# Sheet2_COM.net
KiCad netlist of a schematic drawn in Altium Designer
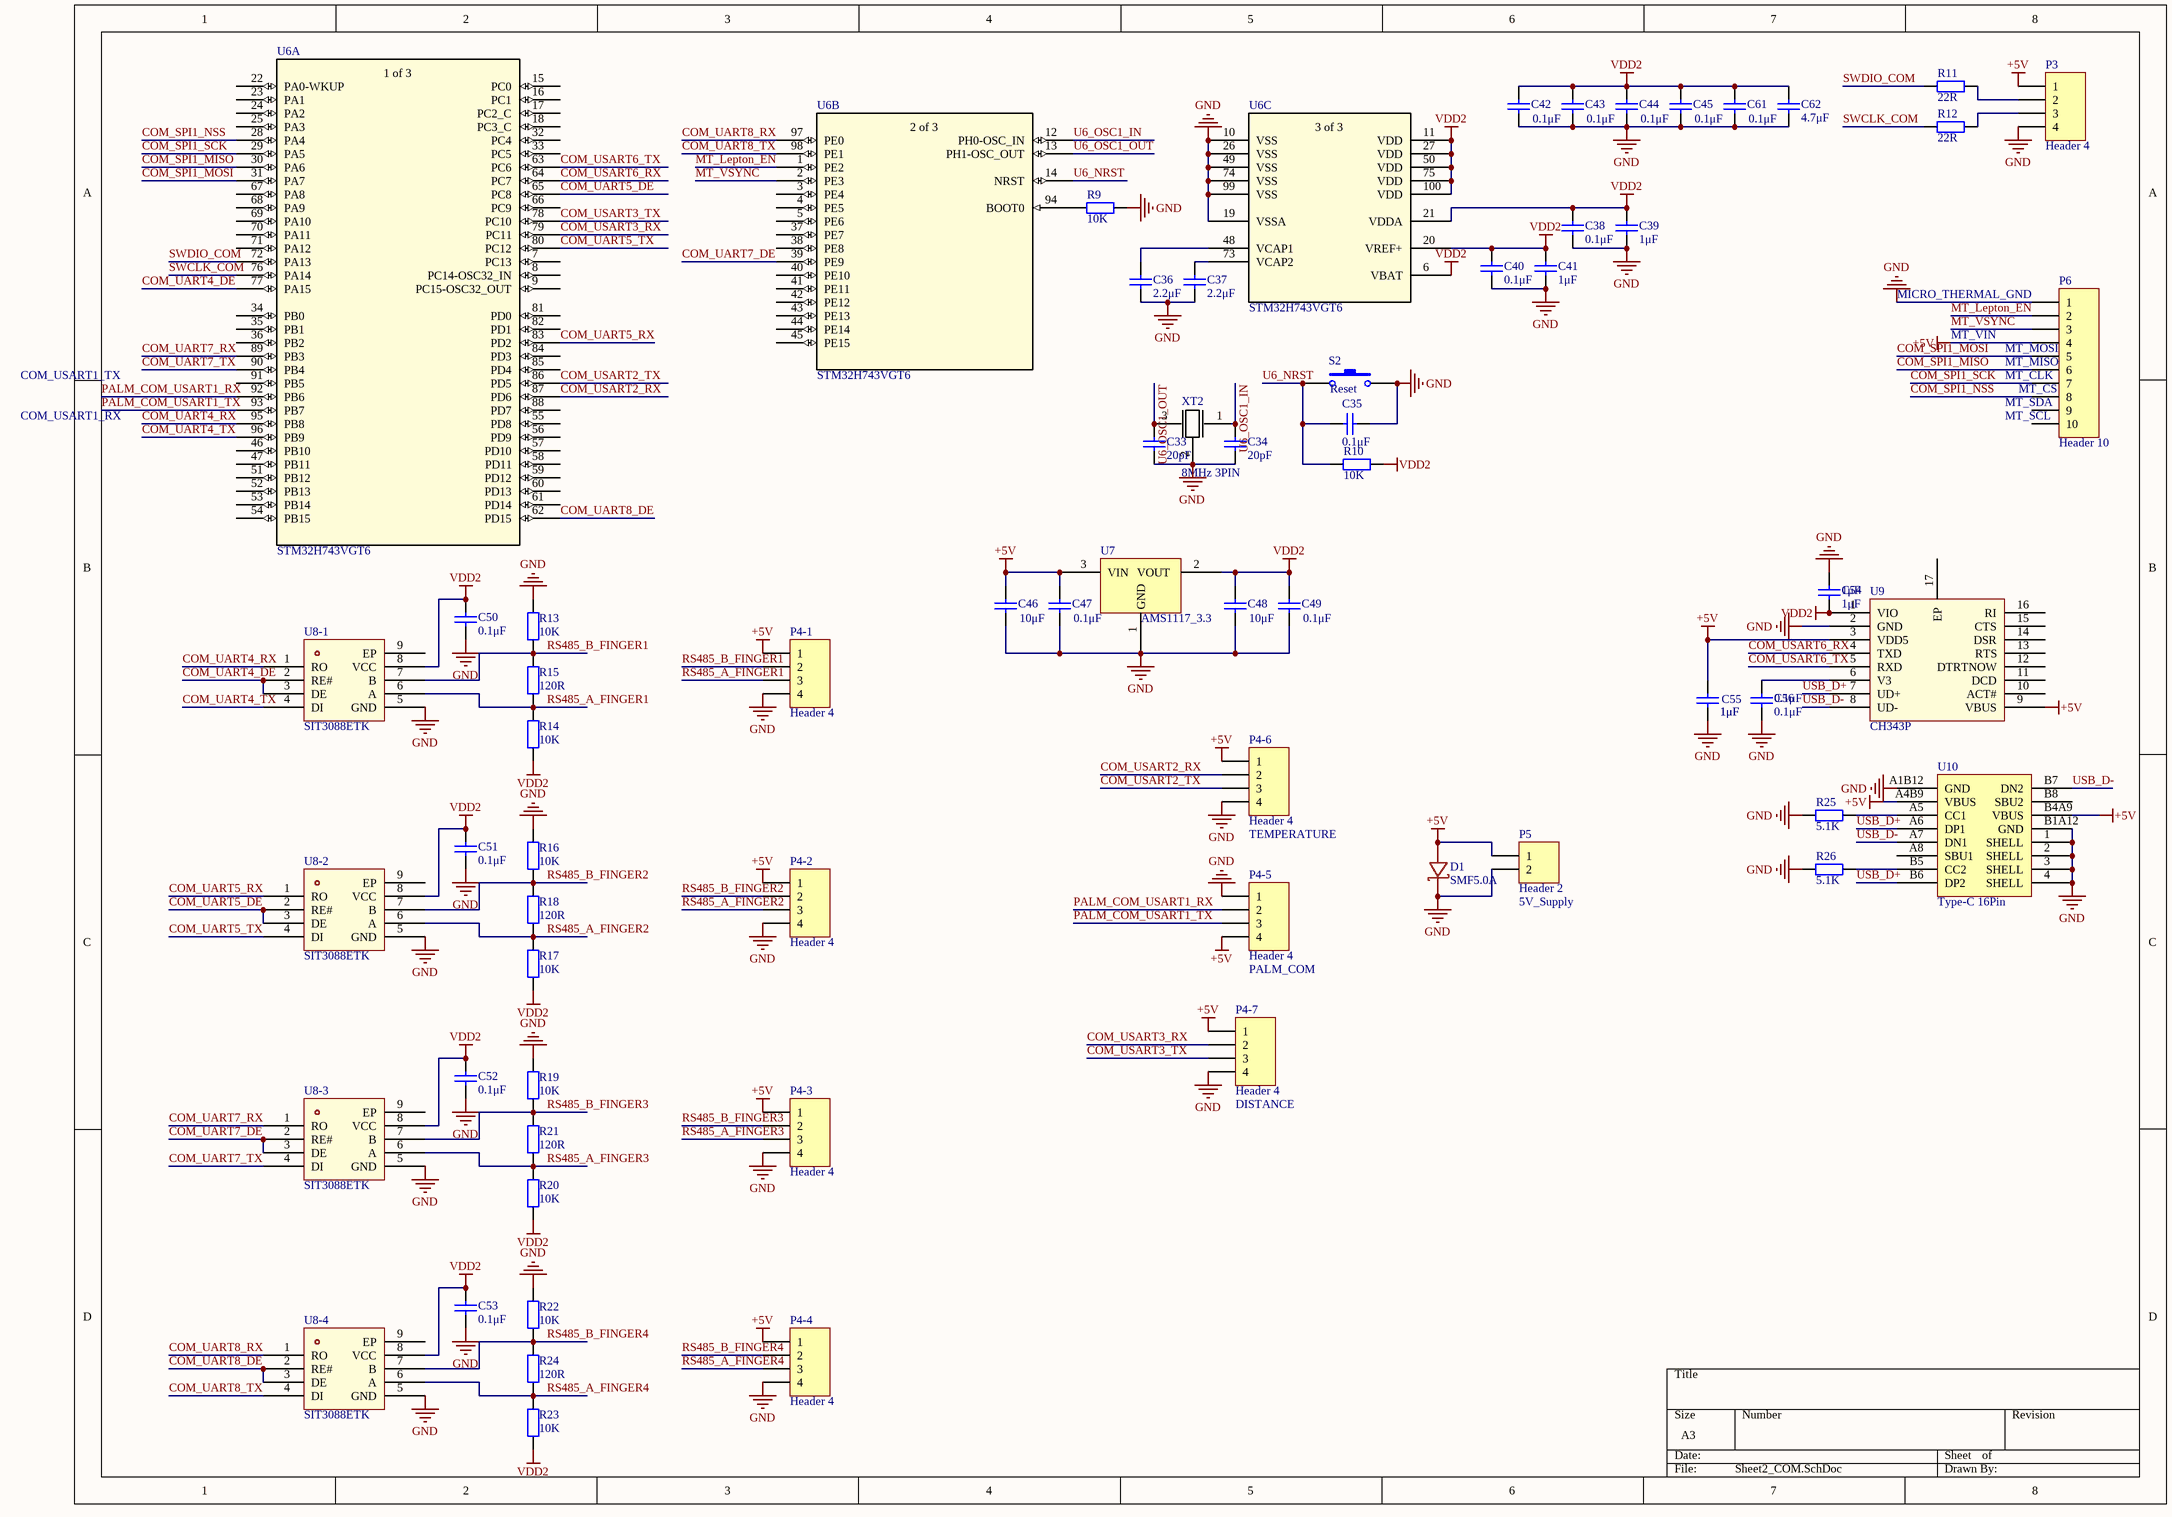
[diagram p0: Sheet2_COM.SchDoc]

(export (version "E")
  (design (tool "Eeschema 10.0.6"))
  (components
    (comp (ref "C33")
      (value "20pF")
      (footprint "C0402")
      (description "Capacitor (Semiconductor SIM Model)")
      (fields (field (name "PUBLISHER") "Altium Limited"))
      (libsource (lib "Miscellaneous Devices") (part "Cap Semi"))
    )
    (comp (ref "C34")
      (value "20pF")
      (footprint "C0402")
      (description "Capacitor (Semiconductor SIM Model)")
      (fields (field (name "PUBLISHER") "Altium Limited"))
      (libsource (lib "Miscellaneous Devices") (part "Cap Semi"))
    )
    (comp (ref "C35")
      (value "0.1μF")
      (footprint "C0402")
      (description "Capacitor (Semiconductor SIM Model)")
      (fields (field (name "PUBLISHER") "Altium Limited"))
      (libsource (lib "Miscellaneous Devices") (part "Cap Semi"))
    )
    (comp (ref "C36")
      (value "2.2μF")
      (footprint "C0402")
      (description "Capacitor (Semiconductor SIM Model)")
      (fields (field (name "PUBLISHER") "Altium Limited"))
      (libsource (lib "Miscellaneous Devices") (part "Cap Semi"))
    )
    (comp (ref "C37")
      (value "2.2μF")
      (footprint "C0402")
      (description "Capacitor (Semiconductor SIM Model)")
      (fields (field (name "PUBLISHER") "Altium Limited"))
      (libsource (lib "Miscellaneous Devices") (part "Cap Semi"))
    )
    (comp (ref "C38")
      (value "0.1μF")
      (footprint "C0402")
      (description "Capacitor (Semiconductor SIM Model)")
      (fields (field (name "PUBLISHER") "Altium Limited"))
      (libsource (lib "Miscellaneous Devices") (part "Cap Semi"))
    )
    (comp (ref "C39")
      (value "1μF")
      (footprint "C0402")
      (description "Capacitor (Semiconductor SIM Model)")
      (fields (field (name "PUBLISHER") "Altium Limited"))
      (libsource (lib "Miscellaneous Devices") (part "Cap Semi"))
    )
    (comp (ref "C40")
      (value "0.1μF")
      (footprint "C0402")
      (description "Capacitor (Semiconductor SIM Model)")
      (fields (field (name "PUBLISHER") "Altium Limited"))
      (libsource (lib "Miscellaneous Devices") (part "Cap Semi"))
    )
    (comp (ref "C41")
      (value "1μF")
      (footprint "C0402")
      (description "Capacitor (Semiconductor SIM Model)")
      (fields (field (name "PUBLISHER") "Altium Limited"))
      (libsource (lib "Miscellaneous Devices") (part "Cap Semi"))
    )
    (comp (ref "C42")
      (value "0.1μF")
      (footprint "C0402")
      (description "Capacitor (Semiconductor SIM Model)")
      (fields (field (name "PUBLISHER") "Altium Limited"))
      (libsource (lib "Miscellaneous Devices") (part "Cap Semi"))
    )
    (comp (ref "C43")
      (value "0.1μF")
      (footprint "C0402")
      (description "Capacitor (Semiconductor SIM Model)")
      (fields (field (name "PUBLISHER") "Altium Limited"))
      (libsource (lib "Miscellaneous Devices") (part "Cap Semi"))
    )
    (comp (ref "C44")
      (value "0.1μF")
      (footprint "C0402")
      (description "Capacitor (Semiconductor SIM Model)")
      (fields (field (name "PUBLISHER") "Altium Limited"))
      (libsource (lib "Miscellaneous Devices") (part "Cap Semi"))
    )
    (comp (ref "C45")
      (value "0.1μF")
      (footprint "C0402")
      (description "Capacitor (Semiconductor SIM Model)")
      (fields (field (name "PUBLISHER") "Altium Limited"))
      (libsource (lib "Miscellaneous Devices") (part "Cap Semi"))
    )
    (comp (ref "C46")
      (value "10μF")
      (footprint "C0402")
      (description "Capacitor (Semiconductor SIM Model)")
      (fields (field (name "PUBLISHER") "Altium Limited"))
      (libsource (lib "Miscellaneous Devices") (part "Cap Semi"))
    )
    (comp (ref "C47")
      (value "0.1μF")
      (footprint "C0402")
      (description "Capacitor (Semiconductor SIM Model)")
      (fields (field (name "PUBLISHER") "Altium Limited"))
      (libsource (lib "Miscellaneous Devices") (part "Cap Semi"))
    )
    (comp (ref "C48")
      (value "10μF")
      (footprint "C0402")
      (description "Capacitor (Semiconductor SIM Model)")
      (fields (field (name "PUBLISHER") "Altium Limited"))
      (libsource (lib "Miscellaneous Devices") (part "Cap Semi"))
    )
    (comp (ref "C49")
      (value "0.1μF")
      (footprint "C0402")
      (description "Capacitor (Semiconductor SIM Model)")
      (fields (field (name "PUBLISHER") "Altium Limited"))
      (libsource (lib "Miscellaneous Devices") (part "Cap Semi"))
    )
    (comp (ref "C50")
      (value "0.1μF")
      (footprint "C0402")
      (description "Capacitor (Semiconductor SIM Model)")
      (fields (field (name "PUBLISHER") "Altium Limited"))
      (libsource (lib "Miscellaneous Devices") (part "Cap Semi"))
    )
    (comp (ref "C51")
      (value "0.1μF")
      (footprint "C0402")
      (description "Capacitor (Semiconductor SIM Model)")
      (fields (field (name "PUBLISHER") "Altium Limited"))
      (libsource (lib "Miscellaneous Devices") (part "Cap Semi"))
    )
    (comp (ref "C52")
      (value "0.1μF")
      (footprint "C0402")
      (description "Capacitor (Semiconductor SIM Model)")
      (fields (field (name "PUBLISHER") "Altium Limited"))
      (libsource (lib "Miscellaneous Devices") (part "Cap Semi"))
    )
    (comp (ref "C53")
      (value "0.1μF")
      (footprint "C0402")
      (description "Capacitor (Semiconductor SIM Model)")
      (fields (field (name "PUBLISHER") "Altium Limited"))
      (libsource (lib "Miscellaneous Devices") (part "Cap Semi"))
    )
    (comp (ref "C54")
      (value "1μF")
      (footprint "C0402")
      (description "Capacitor (Semiconductor SIM Model)")
      (fields (field (name "ALTIUM_VALUE") "1μF") (field (name "PUBLISHER") "Altium Limited"))
      (libsource (lib "Miscellaneous Devices") (part "Cap Semi"))
    )
    (comp (ref "C55")
      (value "1μF")
      (footprint "C0402")
      (description "Capacitor (Semiconductor SIM Model)")
      (fields (field (name "ALTIUM_VALUE") "1μF") (field (name "PUBLISHER") "Altium Limited"))
      (libsource (lib "Miscellaneous Devices") (part "Cap Semi"))
    )
    (comp (ref "C56")
      (value "0.1μF")
      (footprint "C0402")
      (description "Capacitor (Semiconductor SIM Model)")
      (fields (field (name "ALTIUM_VALUE") "0.1μF") (field (name "PUBLISHER") "Altium Limited"))
      (libsource (lib "Miscellaneous Devices") (part "Cap Semi"))
    )
    (comp (ref "C61")
      (value "0.1μF")
      (footprint "C0402")
      (description "Capacitor (Semiconductor SIM Model)")
      (fields (field (name "PUBLISHER") "Altium Limited"))
      (libsource (lib "Miscellaneous Devices") (part "Cap Semi"))
    )
    (comp (ref "C62")
      (value "4.7μF")
      (footprint "C0402")
      (description "Capacitor (Semiconductor SIM Model)")
      (fields (field (name "PUBLISHER") "Altium Limited"))
      (libsource (lib "Miscellaneous Devices") (part "Cap Semi"))
    )
    (comp (ref "D1")
      (value "SMF5.0A")
      (footprint "SOD-123FL_L2.7-W1.8-LS3.8-RD")
      (libsource (lib "Basic") (part "SMF5.0A"))
    )
    (comp (ref "P3")
      (value "Header 4")
      (footprint "CONN-SMD_XDWF-0910-04P")
      (description "XDWF-0910-04P")
      (fields (field (name "PUBLISHER") "Altium Limited"))
      (libsource (lib "Miscellaneous Connectors") (part "Header 4"))
    )
    (comp (ref "P4-1")
      (value "Header 4")
      (footprint "CONN-SMD_XDWF-0910-04P")
      (description "XDWF-0910-04P")
      (fields (field (name "PUBLISHER") "Altium Limited"))
      (libsource (lib "Miscellaneous Connectors") (part "Header 4"))
    )
    (comp (ref "P4-2")
      (value "Header 4")
      (footprint "CONN-SMD_XDWF-0910-04P")
      (description "XDWF-0910-04P")
      (fields (field (name "PUBLISHER") "Altium Limited"))
      (libsource (lib "Miscellaneous Connectors") (part "Header 4"))
    )
    (comp (ref "P4-3")
      (value "Header 4")
      (footprint "CONN-SMD_XDWF-0910-04P")
      (description "XDWF-0910-04P")
      (fields (field (name "PUBLISHER") "Altium Limited"))
      (libsource (lib "Miscellaneous Connectors") (part "Header 4"))
    )
    (comp (ref "P4-4")
      (value "Header 4")
      (footprint "CONN-SMD_XDWF-0910-04P")
      (description "XDWF-0910-04P")
      (fields (field (name "PUBLISHER") "Altium Limited"))
      (libsource (lib "Miscellaneous Connectors") (part "Header 4"))
    )
    (comp (ref "P4-5")
      (value "Header 4")
      (footprint "HDR1X4")
      (description "Header, 4-Pin")
      (fields (field (name "PUBLISHER") "Altium Limited"))
      (libsource (lib "Miscellaneous Connectors") (part "Header 4"))
    )
    (comp (ref "P4-6")
      (value "Header 4")
      (footprint "CONN-SMD_XDWF-0910-04P")
      (description "XDWF-0910-04P")
      (fields (field (name "PUBLISHER") "Altium Limited"))
      (libsource (lib "Miscellaneous Connectors") (part "Header 4"))
    )
    (comp (ref "P4-7")
      (value "Header 4")
      (footprint "CONN-SMD_XDWF-0910-04P")
      (description "XDWF-0910-04P")
      (fields (field (name "PUBLISHER") "Altium Limited"))
      (libsource (lib "Miscellaneous Connectors") (part "Header 4"))
    )
    (comp (ref "P5")
      (value "Header 2")
      (footprint "CONN-SMD_2060-452")
      (description "Header, 2-Pin")
      (fields (field (name "PUBLISHER") "Altium Limited"))
      (libsource (lib "Miscellaneous Connectors") (part "Header 2"))
    )
    (comp (ref "P6")
      (value "Header 10")
      (footprint "FPC-SMD_10P-P0.50_HCTL_HC-FPC-05-10-10RLTAG")
      (description "Header, 10-Pin")
      (fields (field (name "PUBLISHER") "Altium Limited"))
      (libsource (lib "Miscellaneous Connectors") (part "Header 10"))
    )
    (comp (ref "R9")
      (value "10K")
      (footprint "R0402")
      (description "Resistor")
      (fields (field (name "PUBLISHER") "Altium Limited"))
      (libsource (lib "") (part "Res2_3"))
    )
    (comp (ref "R10")
      (value "10K")
      (footprint "R0402")
      (description "Resistor")
      (fields (field (name "PUBLISHER") "Altium Limited"))
      (libsource (lib "Miscellaneous Devices") (part "Res2"))
    )
    (comp (ref "R11")
      (value "22R")
      (footprint "R0402")
      (description "Resistor")
      (fields (field (name "PUBLISHER") "Altium Limited"))
      (libsource (lib "Miscellaneous Devices") (part "Res2"))
    )
    (comp (ref "R12")
      (value "22R")
      (footprint "R0402")
      (description "Resistor")
      (fields (field (name "PUBLISHER") "Altium Limited"))
      (libsource (lib "Miscellaneous Devices") (part "Res2"))
    )
    (comp (ref "R13")
      (value "10K")
      (footprint "R0402")
      (description "Resistor")
      (fields (field (name "PUBLISHER") "Altium Limited"))
      (libsource (lib "") (part "Res2_1"))
    )
    (comp (ref "R14")
      (value "10K")
      (footprint "R0402")
      (description "Resistor")
      (fields (field (name "PUBLISHER") "Altium Limited"))
      (libsource (lib "") (part "Res2_1"))
    )
    (comp (ref "R15")
      (value "120R")
      (footprint "R0402")
      (description "Resistor")
      (fields (field (name "PUBLISHER") "Altium Limited"))
      (libsource (lib "") (part "Res2_2"))
    )
    (comp (ref "R16")
      (value "10K")
      (footprint "R0402")
      (description "Resistor")
      (fields (field (name "PUBLISHER") "Altium Limited"))
      (libsource (lib "") (part "Res2_1"))
    )
    (comp (ref "R17")
      (value "10K")
      (footprint "R0402")
      (description "Resistor")
      (fields (field (name "PUBLISHER") "Altium Limited"))
      (libsource (lib "") (part "Res2_1"))
    )
    (comp (ref "R18")
      (value "120R")
      (footprint "R0402")
      (description "Resistor")
      (fields (field (name "PUBLISHER") "Altium Limited"))
      (libsource (lib "") (part "Res2_2"))
    )
    (comp (ref "R19")
      (value "10K")
      (footprint "R0402")
      (description "Resistor")
      (fields (field (name "PUBLISHER") "Altium Limited"))
      (libsource (lib "") (part "Res2_1"))
    )
    (comp (ref "R20")
      (value "10K")
      (footprint "R0402")
      (description "Resistor")
      (fields (field (name "PUBLISHER") "Altium Limited"))
      (libsource (lib "") (part "Res2_1"))
    )
    (comp (ref "R21")
      (value "120R")
      (footprint "R0402")
      (description "Resistor")
      (fields (field (name "PUBLISHER") "Altium Limited"))
      (libsource (lib "") (part "Res2_2"))
    )
    (comp (ref "R22")
      (value "10K")
      (footprint "R0402")
      (description "Resistor")
      (fields (field (name "PUBLISHER") "Altium Limited"))
      (libsource (lib "") (part "Res2_1"))
    )
    (comp (ref "R23")
      (value "10K")
      (footprint "R0402")
      (description "Resistor")
      (fields (field (name "PUBLISHER") "Altium Limited"))
      (libsource (lib "") (part "Res2_1"))
    )
    (comp (ref "R24")
      (value "120R")
      (footprint "R0402")
      (description "Resistor")
      (fields (field (name "PUBLISHER") "Altium Limited"))
      (libsource (lib "") (part "Res2_2"))
    )
    (comp (ref "R25")
      (value "5.1K")
      (footprint "R0402")
      (description "Resistor")
      (fields (field (name "PUBLISHER") "Altium Limited"))
      (libsource (lib "Miscellaneous Devices") (part "Res2"))
    )
    (comp (ref "R26")
      (value "5.1K")
      (footprint "R0402")
      (description "Resistor")
      (fields (field (name "PUBLISHER") "Altium Limited"))
      (libsource (lib "Miscellaneous Devices") (part "Res2"))
    )
    (comp (ref "S2")
      (value "Reset")
      (footprint "SW-SMD_L3.9-W3.0-P4.45")
      (description "TS-1088R-02026")
      (fields (field (name "PUBLISHER") "Altium Limited"))
      (libsource (lib "Miscellaneous Devices") (part "SW-PB"))
    )
    (comp (ref "U6")
      (value "STM32H743VGT6")
      (footprint "LQFP100-14x14mm")
      (description "No Description Available")
      (libsource (lib "STM32H743VGT6") (part "STM32H743VGT6"))
    )
    (comp (ref "U7")
      (value "AMS1117_3.3")
      (footprint "AMS1117-3.3")
      (libsource (lib "Schlib1") (part "AMS1117_3.3 SOT-89"))
    )
    (comp (ref "U8-1")
      (value "SIT3088ETK")
      (footprint "DFN-8_L3.0-W3.0-P0.65-BL-EP")
      (libsource (lib "Basic") (part "SIT3088ETK"))
    )
    (comp (ref "U8-2")
      (value "SIT3088ETK")
      (footprint "DFN-8_L3.0-W3.0-P0.65-BL-EP")
      (libsource (lib "Basic") (part "SIT3088ETK"))
    )
    (comp (ref "U8-3")
      (value "SIT3088ETK")
      (footprint "DFN-8_L3.0-W3.0-P0.65-BL-EP")
      (libsource (lib "Basic") (part "SIT3088ETK"))
    )
    (comp (ref "U8-4")
      (value "SIT3088ETK")
      (footprint "DFN-8_L3.0-W3.0-P0.65-BL-EP")
      (libsource (lib "Basic") (part "SIT3088ETK"))
    )
    (comp (ref "U9") (value "CH343P") (footprint "CH343P") (libsource (lib "Schlibs") (part "CH343P")))
    (comp (ref "U10")
      (value "Type-C 16Pin")
      (footprint "USB-C-SMD_TYPE-C16PIN")
      (libsource (lib "Schlib1") (part "Type-C 16Pin"))
    )
    (comp (ref "XT2")
      (value "8MHz 3PIN")
      (footprint "8MHz 0.07% OSC-SMD_3P-L3.2-W1.3-P1.20-L")
      (description "CSTNE8M00GH5C000R0")
      (libsource (lib "Schlibs") (part "8MHz 0.07% 3PIN_1"))
    )
  )
  (nets
    (net (code "1") (name "+5V") (class "Default")
      (node (ref "C46") (pin "2") (pinfunction "2_2") (pintype "passive"))
      (node (ref "C47") (pin "2") (pinfunction "2_2") (pintype "passive"))
      (node (ref "C55") (pin "2") (pinfunction "2_2") (pintype "passive"))
      (node (ref "D1") (pin "2") (pinfunction "A_2") (pintype "passive"))
      (node (ref "P3") (pin "1") (pinfunction "1_1") (pintype "passive"))
      (node (ref "P4-1") (pin "1") (pinfunction "1_1") (pintype "passive"))
      (node (ref "P4-2") (pin "1") (pinfunction "1_1") (pintype "passive"))
      (node (ref "P4-3") (pin "1") (pinfunction "1_1") (pintype "passive"))
      (node (ref "P4-4") (pin "1") (pinfunction "1_1") (pintype "passive"))
      (node (ref "P4-5") (pin "4") (pinfunction "4_4") (pintype "passive"))
      (node (ref "P4-6") (pin "1") (pinfunction "1_1") (pintype "passive"))
      (node (ref "P4-7") (pin "1") (pinfunction "1_1") (pintype "passive"))
      (node (ref "P5") (pin "1") (pinfunction "1_1") (pintype "passive"))
      (node (ref "P6") (pin "4") (pinfunction "4_4") (pintype "passive"))
      (node (ref "U10") (pin "A4B9") (pinfunction "VBUS_A4B9") (pintype "passive"))
      (node (ref "U10") (pin "B4A9") (pinfunction "VBUS_B4A9") (pintype "passive"))
      (node (ref "U7") (pin "3") (pinfunction "VIN_3") (pintype "passive"))
      (node (ref "U9") (pin "3") (pinfunction "VDD5_3") (pintype "passive"))
      (node (ref "U9") (pin "9") (pinfunction "VBUS_9") (pintype "passive"))
    )
    (net (code "2") (name "/COM_SPI1_MISO") (class "Default")
      (node (ref "P6") (pin "6") (pinfunction "6_6") (pintype "passive"))
      (node (ref "U6") (pin "30") (pinfunction "PA6_30") (pintype "bidirectional"))
    )
    (net (code "3") (name "/COM_SPI1_MOSI") (class "Default")
      (node (ref "P6") (pin "5") (pinfunction "5_5") (pintype "passive"))
      (node (ref "U6") (pin "31") (pinfunction "PA7_31") (pintype "bidirectional"))
    )
    (net (code "4") (name "/COM_SPI1_NSS") (class "Default")
      (node (ref "P6") (pin "8") (pinfunction "8_8") (pintype "passive"))
      (node (ref "U6") (pin "28") (pinfunction "PA4_28") (pintype "bidirectional"))
    )
    (net (code "5") (name "/COM_SPI1_SCK") (class "Default")
      (node (ref "P6") (pin "7") (pinfunction "7_7") (pintype "passive"))
      (node (ref "U6") (pin "29") (pinfunction "PA5_29") (pintype "bidirectional"))
    )
    (net (code "6") (name "/COM_UART4_DE") (class "Default")
      (node (ref "U6") (pin "77") (pinfunction "PA15_77") (pintype "bidirectional"))
      (node (ref "U8-1") (pin "2") (pinfunction "RE#_2") (pintype "passive"))
      (node (ref "U8-1") (pin "3") (pinfunction "DE_3") (pintype "passive"))
    )
    (net (code "7") (name "/COM_UART4_RX") (class "Default")
      (node (ref "U6") (pin "95") (pinfunction "PB8_95") (pintype "bidirectional"))
      (node (ref "U8-1") (pin "1") (pinfunction "RO_1") (pintype "passive"))
    )
    (net (code "8") (name "/COM_UART4_TX") (class "Default")
      (node (ref "U6") (pin "96") (pinfunction "PB9_96") (pintype "bidirectional"))
      (node (ref "U8-1") (pin "4") (pinfunction "DI_4") (pintype "passive"))
    )
    (net (code "9") (name "/COM_UART5_DE") (class "Default")
      (node (ref "U6") (pin "65") (pinfunction "PC8_65") (pintype "bidirectional"))
      (node (ref "U8-2") (pin "2") (pinfunction "RE#_2") (pintype "passive"))
      (node (ref "U8-2") (pin "3") (pinfunction "DE_3") (pintype "passive"))
    )
    (net (code "10") (name "/COM_UART5_RX") (class "Default")
      (node (ref "U6") (pin "83") (pinfunction "PD2_83") (pintype "bidirectional"))
      (node (ref "U8-2") (pin "1") (pinfunction "RO_1") (pintype "passive"))
    )
    (net (code "11") (name "/COM_UART5_TX") (class "Default")
      (node (ref "U6") (pin "80") (pinfunction "PC12_80") (pintype "bidirectional"))
      (node (ref "U8-2") (pin "4") (pinfunction "DI_4") (pintype "passive"))
    )
    (net (code "12") (name "/COM_UART7_DE") (class "Default")
      (node (ref "U6") (pin "39") (pinfunction "PE9_39") (pintype "bidirectional"))
      (node (ref "U8-3") (pin "2") (pinfunction "RE#_2") (pintype "passive"))
      (node (ref "U8-3") (pin "3") (pinfunction "DE_3") (pintype "passive"))
    )
    (net (code "13") (name "/COM_UART7_RX") (class "Default")
      (node (ref "U6") (pin "89") (pinfunction "PB3_89") (pintype "bidirectional"))
      (node (ref "U8-3") (pin "1") (pinfunction "RO_1") (pintype "passive"))
    )
    (net (code "14") (name "/COM_UART7_TX") (class "Default")
      (node (ref "U6") (pin "90") (pinfunction "PB4_90") (pintype "bidirectional"))
      (node (ref "U8-3") (pin "4") (pinfunction "DI_4") (pintype "passive"))
    )
    (net (code "15") (name "/COM_UART8_DE") (class "Default")
      (node (ref "U6") (pin "62") (pinfunction "PD15_62") (pintype "bidirectional"))
      (node (ref "U8-4") (pin "2") (pinfunction "RE#_2") (pintype "passive"))
      (node (ref "U8-4") (pin "3") (pinfunction "DE_3") (pintype "passive"))
    )
    (net (code "16") (name "/COM_UART8_RX") (class "Default")
      (node (ref "U6") (pin "97") (pinfunction "PE0_97") (pintype "bidirectional"))
      (node (ref "U8-4") (pin "1") (pinfunction "RO_1") (pintype "passive"))
    )
    (net (code "17") (name "/COM_UART8_TX") (class "Default")
      (node (ref "U6") (pin "98") (pinfunction "PE1_98") (pintype "bidirectional"))
      (node (ref "U8-4") (pin "4") (pinfunction "DI_4") (pintype "passive"))
    )
    (net (code "18") (name "/COM_USART2_RX") (class "Default")
      (node (ref "P4-6") (pin "2") (pinfunction "2_2") (pintype "passive"))
      (node (ref "U6") (pin "87") (pinfunction "PD6_87") (pintype "bidirectional"))
    )
    (net (code "19") (name "/COM_USART2_TX") (class "Default")
      (node (ref "P4-6") (pin "3") (pinfunction "3_3") (pintype "passive"))
      (node (ref "U6") (pin "86") (pinfunction "PD5_86") (pintype "bidirectional"))
    )
    (net (code "20") (name "/COM_USART3_RX") (class "Default")
      (node (ref "P4-7") (pin "2") (pinfunction "2_2") (pintype "passive"))
      (node (ref "U6") (pin "79") (pinfunction "PC11_79") (pintype "bidirectional"))
    )
    (net (code "21") (name "/COM_USART3_TX") (class "Default")
      (node (ref "P4-7") (pin "3") (pinfunction "3_3") (pintype "passive"))
      (node (ref "U6") (pin "78") (pinfunction "PC10_78") (pintype "bidirectional"))
    )
    (net (code "22") (name "/COM_USART6_RX") (class "Default")
      (node (ref "U6") (pin "64") (pinfunction "PC7_64") (pintype "bidirectional"))
      (node (ref "U9") (pin "4") (pinfunction "TXD_4") (pintype "passive"))
    )
    (net (code "23") (name "/COM_USART6_TX") (class "Default")
      (node (ref "U6") (pin "63") (pinfunction "PC6_63") (pintype "bidirectional"))
      (node (ref "U9") (pin "5") (pinfunction "RXD_5") (pintype "passive"))
    )
    (net (code "24") (name "/MT_Lepton_EN") (class "Default")
      (node (ref "P6") (pin "2") (pinfunction "2_2") (pintype "passive"))
      (node (ref "U6") (pin "1") (pinfunction "PE2_1") (pintype "bidirectional"))
    )
    (net (code "25") (name "/MT_VSYNC") (class "Default")
      (node (ref "P6") (pin "3") (pinfunction "3_3") (pintype "passive"))
      (node (ref "U6") (pin "2") (pinfunction "PE3_2") (pintype "bidirectional"))
    )
    (net (code "26") (name "/PALM_COM_USART1_RX") (class "Default")
      (node (ref "P4-5") (pin "2") (pinfunction "2_2") (pintype "passive"))
      (node (ref "U6") (pin "92") (pinfunction "PB6_92") (pintype "bidirectional"))
    )
    (net (code "27") (name "/PALM_COM_USART1_TX") (class "Default")
      (node (ref "P4-5") (pin "3") (pinfunction "3_3") (pintype "passive"))
      (node (ref "U6") (pin "93") (pinfunction "PB7_93") (pintype "bidirectional"))
    )
    (net (code "28") (name "/RS485_A_FINGER1") (class "Default")
      (node (ref "P4-1") (pin "3") (pinfunction "3_3") (pintype "passive"))
      (node (ref "R14") (pin "1") (pinfunction "1_1") (pintype "passive"))
      (node (ref "R15") (pin "1") (pinfunction "1_1") (pintype "passive"))
      (node (ref "U8-1") (pin "6") (pinfunction "A_6") (pintype "passive"))
    )
    (net (code "29") (name "/RS485_A_FINGER2") (class "Default")
      (node (ref "P4-2") (pin "3") (pinfunction "3_3") (pintype "passive"))
      (node (ref "R17") (pin "1") (pinfunction "1_1") (pintype "passive"))
      (node (ref "R18") (pin "1") (pinfunction "1_1") (pintype "passive"))
      (node (ref "U8-2") (pin "6") (pinfunction "A_6") (pintype "passive"))
    )
    (net (code "30") (name "/RS485_A_FINGER3") (class "Default")
      (node (ref "P4-3") (pin "3") (pinfunction "3_3") (pintype "passive"))
      (node (ref "R20") (pin "1") (pinfunction "1_1") (pintype "passive"))
      (node (ref "R21") (pin "1") (pinfunction "1_1") (pintype "passive"))
      (node (ref "U8-3") (pin "6") (pinfunction "A_6") (pintype "passive"))
    )
    (net (code "31") (name "/RS485_A_FINGER4") (class "Default")
      (node (ref "P4-4") (pin "3") (pinfunction "3_3") (pintype "passive"))
      (node (ref "R23") (pin "1") (pinfunction "1_1") (pintype "passive"))
      (node (ref "R24") (pin "1") (pinfunction "1_1") (pintype "passive"))
      (node (ref "U8-4") (pin "6") (pinfunction "A_6") (pintype "passive"))
    )
    (net (code "32") (name "/RS485_B_FINGER1") (class "Default")
      (node (ref "P4-1") (pin "2") (pinfunction "2_2") (pintype "passive"))
      (node (ref "R13") (pin "2") (pinfunction "2_2") (pintype "passive"))
      (node (ref "R15") (pin "2") (pinfunction "2_2") (pintype "passive"))
      (node (ref "U8-1") (pin "7") (pinfunction "B_7") (pintype "passive"))
    )
    (net (code "33") (name "/RS485_B_FINGER2") (class "Default")
      (node (ref "P4-2") (pin "2") (pinfunction "2_2") (pintype "passive"))
      (node (ref "R16") (pin "2") (pinfunction "2_2") (pintype "passive"))
      (node (ref "R18") (pin "2") (pinfunction "2_2") (pintype "passive"))
      (node (ref "U8-2") (pin "7") (pinfunction "B_7") (pintype "passive"))
    )
    (net (code "34") (name "/RS485_B_FINGER3") (class "Default")
      (node (ref "P4-3") (pin "2") (pinfunction "2_2") (pintype "passive"))
      (node (ref "R19") (pin "2") (pinfunction "2_2") (pintype "passive"))
      (node (ref "R21") (pin "2") (pinfunction "2_2") (pintype "passive"))
      (node (ref "U8-3") (pin "7") (pinfunction "B_7") (pintype "passive"))
    )
    (net (code "35") (name "/RS485_B_FINGER4") (class "Default")
      (node (ref "P4-4") (pin "2") (pinfunction "2_2") (pintype "passive"))
      (node (ref "R22") (pin "2") (pinfunction "2_2") (pintype "passive"))
      (node (ref "R24") (pin "2") (pinfunction "2_2") (pintype "passive"))
      (node (ref "U8-4") (pin "7") (pinfunction "B_7") (pintype "passive"))
    )
    (net (code "36") (name "/SWCLK_COM") (class "Default")
      (node (ref "R12") (pin "1") (pinfunction "1_1") (pintype "passive"))
      (node (ref "U6") (pin "76") (pinfunction "PA14_76") (pintype "bidirectional"))
    )
    (net (code "37") (name "/SWDIO_COM") (class "Default")
      (node (ref "R11") (pin "1") (pinfunction "1_1") (pintype "passive"))
      (node (ref "U6") (pin "72") (pinfunction "PA13_72") (pintype "bidirectional"))
    )
    (net (code "38") (name "/U6_NRST") (class "Default")
      (node (ref "C35") (pin "1") (pinfunction "1_1") (pintype "passive"))
      (node (ref "R10") (pin "1") (pinfunction "1_1") (pintype "passive"))
      (node (ref "S2") (pin "1") (pinfunction "1_1") (pintype "passive"))
      (node (ref "U6") (pin "14") (pinfunction "NRST_14") (pintype "bidirectional"))
    )
    (net (code "39") (name "/U6_OSC1_IN") (class "Default")
      (node (ref "C34") (pin "2") (pinfunction "2_2") (pintype "passive"))
      (node (ref "U6") (pin "12") (pinfunction "PH0-OSC_IN_12") (pintype "bidirectional"))
      (node (ref "XT2") (pin "1") (pinfunction "OUTPUT_1") (pintype "passive"))
    )
    (net (code "40") (name "/U6_OSC1_OUT") (class "Default")
      (node (ref "C33") (pin "2") (pinfunction "2_2") (pintype "passive"))
      (node (ref "U6") (pin "13") (pinfunction "PH1-OSC_OUT_13") (pintype "bidirectional"))
      (node (ref "XT2") (pin "3") (pinfunction "INPUT_3") (pintype "passive"))
    )
    (net (code "41") (name "/USB_D+") (class "Default")
      (node (ref "U10") (pin "A6") (pinfunction "DP1_A6") (pintype "passive"))
      (node (ref "U10") (pin "B6") (pinfunction "DP2_B6") (pintype "passive"))
      (node (ref "U9") (pin "7") (pinfunction "UD+_7") (pintype "passive"))
    )
    (net (code "42") (name "/USB_D-") (class "Default")
      (node (ref "U10") (pin "A7") (pinfunction "DN1_A7") (pintype "passive"))
      (node (ref "U10") (pin "B7") (pinfunction "DN2_B7") (pintype "passive"))
      (node (ref "U9") (pin "8") (pinfunction "UD-_8") (pintype "passive"))
    )
    (net (code "43") (name "GND") (class "Default")
      (node (ref "C33") (pin "1") (pinfunction "1_1") (pintype "passive"))
      (node (ref "C34") (pin "1") (pinfunction "1_1") (pintype "passive"))
      (node (ref "C35") (pin "2") (pinfunction "2_2") (pintype "passive"))
      (node (ref "C36") (pin "1") (pinfunction "1_1") (pintype "passive"))
      (node (ref "C37") (pin "1") (pinfunction "1_1") (pintype "passive"))
      (node (ref "C38") (pin "2") (pinfunction "2_2") (pintype "passive"))
      (node (ref "C39") (pin "2") (pinfunction "2_2") (pintype "passive"))
      (node (ref "C40") (pin "2") (pinfunction "2_2") (pintype "passive"))
      (node (ref "C41") (pin "2") (pinfunction "2_2") (pintype "passive"))
      (node (ref "C42") (pin "1") (pinfunction "1_1") (pintype "passive"))
      (node (ref "C43") (pin "1") (pinfunction "1_1") (pintype "passive"))
      (node (ref "C44") (pin "1") (pinfunction "1_1") (pintype "passive"))
      (node (ref "C45") (pin "1") (pinfunction "1_1") (pintype "passive"))
      (node (ref "C46") (pin "1") (pinfunction "1_1") (pintype "passive"))
      (node (ref "C47") (pin "1") (pinfunction "1_1") (pintype "passive"))
      (node (ref "C48") (pin "1") (pinfunction "1_1") (pintype "passive"))
      (node (ref "C49") (pin "1") (pinfunction "1_1") (pintype "passive"))
      (node (ref "C50") (pin "1") (pinfunction "1_1") (pintype "passive"))
      (node (ref "C51") (pin "1") (pinfunction "1_1") (pintype "passive"))
      (node (ref "C52") (pin "1") (pinfunction "1_1") (pintype "passive"))
      (node (ref "C53") (pin "1") (pinfunction "1_1") (pintype "passive"))
      (node (ref "C54") (pin "1") (pinfunction "1_1") (pintype "passive"))
      (node (ref "C55") (pin "1") (pinfunction "1_1") (pintype "passive"))
      (node (ref "C56") (pin "1") (pinfunction "1_1") (pintype "passive"))
      (node (ref "C61") (pin "1") (pinfunction "1_1") (pintype "passive"))
      (node (ref "C62") (pin "2") (pinfunction "2_2") (pintype "passive"))
      (node (ref "D1") (pin "1") (pinfunction "K_1") (pintype "passive"))
      (node (ref "P3") (pin "4") (pinfunction "4_4") (pintype "passive"))
      (node (ref "P4-1") (pin "4") (pinfunction "4_4") (pintype "passive"))
      (node (ref "P4-2") (pin "4") (pinfunction "4_4") (pintype "passive"))
      (node (ref "P4-3") (pin "4") (pinfunction "4_4") (pintype "passive"))
      (node (ref "P4-4") (pin "4") (pinfunction "4_4") (pintype "passive"))
      (node (ref "P4-5") (pin "1") (pinfunction "1_1") (pintype "passive"))
      (node (ref "P4-6") (pin "4") (pinfunction "4_4") (pintype "passive"))
      (node (ref "P4-7") (pin "4") (pinfunction "4_4") (pintype "passive"))
      (node (ref "P5") (pin "2") (pinfunction "2_2") (pintype "passive"))
      (node (ref "P6") (pin "1") (pinfunction "1_1") (pintype "passive"))
      (node (ref "R13") (pin "1") (pinfunction "1_1") (pintype "passive"))
      (node (ref "R16") (pin "1") (pinfunction "1_1") (pintype "passive"))
      (node (ref "R19") (pin "1") (pinfunction "1_1") (pintype "passive"))
      (node (ref "R22") (pin "1") (pinfunction "1_1") (pintype "passive"))
      (node (ref "R25") (pin "1") (pinfunction "1_1") (pintype "passive"))
      (node (ref "R26") (pin "1") (pinfunction "1_1") (pintype "passive"))
      (node (ref "R9") (pin "1") (pinfunction "1_1") (pintype "passive"))
      (node (ref "S2") (pin "2") (pinfunction "2_2") (pintype "passive"))
      (node (ref "U10") (pin "1") (pinfunction "SHELL_1") (pintype "passive"))
      (node (ref "U10") (pin "2") (pinfunction "SHELL_2") (pintype "passive"))
      (node (ref "U10") (pin "3") (pinfunction "SHELL_3") (pintype "passive"))
      (node (ref "U10") (pin "4") (pinfunction "SHELL_4") (pintype "passive"))
      (node (ref "U10") (pin "A1B12") (pinfunction "GND_A1B12") (pintype "passive"))
      (node (ref "U10") (pin "B1A12") (pinfunction "GND_B1A12") (pintype "passive"))
      (node (ref "U6") (pin "10") (pinfunction "VSS_10") (pintype "power_in"))
      (node (ref "U6") (pin "19") (pinfunction "VSSA_19") (pintype "power_in"))
      (node (ref "U6") (pin "26") (pinfunction "VSS_26") (pintype "power_in"))
      (node (ref "U6") (pin "49") (pinfunction "VSS_49") (pintype "power_in"))
      (node (ref "U6") (pin "74") (pinfunction "VSS_74") (pintype "power_in"))
      (node (ref "U6") (pin "99") (pinfunction "VSS_99") (pintype "power_in"))
      (node (ref "U7") (pin "1") (pinfunction "GND_1") (pintype "passive"))
      (node (ref "U8-1") (pin "5") (pinfunction "GND_5") (pintype "passive"))
      (node (ref "U8-2") (pin "5") (pinfunction "GND_5") (pintype "passive"))
      (node (ref "U8-3") (pin "5") (pinfunction "GND_5") (pintype "passive"))
      (node (ref "U8-4") (pin "5") (pinfunction "GND_5") (pintype "passive"))
      (node (ref "U9") (pin "2") (pinfunction "GND_2") (pintype "passive"))
      (node (ref "XT2") (pin "2") (pinfunction "GND_2") (pintype "passive"))
    )
    (net (code "44") (name "Net-(P3-Pad2)") (class "Default")
      (node (ref "P3") (pin "2") (pinfunction "2_2") (pintype "passive"))
      (node (ref "R11") (pin "2") (pinfunction "2_2") (pintype "passive"))
    )
    (net (code "45") (name "Net-(P3-Pad3)") (class "Default")
      (node (ref "P3") (pin "3") (pinfunction "3_3") (pintype "passive"))
      (node (ref "R12") (pin "2") (pinfunction "2_2") (pintype "passive"))
    )
    (net (code "46") (name "Net-(U6B-BOOT0)") (class "Default")
      (node (ref "R9") (pin "2") (pinfunction "2_2") (pintype "passive"))
      (node (ref "U6") (pin "94") (pinfunction "BOOT0_94") (pintype "input"))
    )
    (net (code "47") (name "Net-(U6C-VCAP1)") (class "Default")
      (node (ref "C36") (pin "2") (pinfunction "2_2") (pintype "passive"))
      (node (ref "U6") (pin "48") (pinfunction "VCAP1_48") (pintype "power_in"))
    )
    (net (code "48") (name "Net-(U6C-VCAP2)") (class "Default")
      (node (ref "C37") (pin "2") (pinfunction "2_2") (pintype "passive"))
      (node (ref "U6") (pin "73") (pinfunction "VCAP2_73") (pintype "power_in"))
    )
    (net (code "49") (name "Net-(U9-V3)") (class "Default")
      (node (ref "C56") (pin "2") (pinfunction "2_2") (pintype "passive"))
      (node (ref "U9") (pin "6") (pinfunction "V3_6") (pintype "passive"))
    )
    (net (code "50") (name "Net-(U10-CC1)") (class "Default")
      (node (ref "R25") (pin "2") (pinfunction "2_2") (pintype "passive"))
      (node (ref "U10") (pin "A5") (pinfunction "CC1_A5") (pintype "passive"))
    )
    (net (code "51") (name "Net-(U10-CC2)") (class "Default")
      (node (ref "R26") (pin "2") (pinfunction "2_2") (pintype "passive"))
      (node (ref "U10") (pin "B5") (pinfunction "CC2_B5") (pintype "passive"))
    )
    (net (code "52") (name "VDD2") (class "Default")
      (node (ref "C38") (pin "1") (pinfunction "1_1") (pintype "passive"))
      (node (ref "C39") (pin "1") (pinfunction "1_1") (pintype "passive"))
      (node (ref "C40") (pin "1") (pinfunction "1_1") (pintype "passive"))
      (node (ref "C41") (pin "1") (pinfunction "1_1") (pintype "passive"))
      (node (ref "C42") (pin "2") (pinfunction "2_2") (pintype "passive"))
      (node (ref "C43") (pin "2") (pinfunction "2_2") (pintype "passive"))
      (node (ref "C44") (pin "2") (pinfunction "2_2") (pintype "passive"))
      (node (ref "C45") (pin "2") (pinfunction "2_2") (pintype "passive"))
      (node (ref "C48") (pin "2") (pinfunction "2_2") (pintype "passive"))
      (node (ref "C49") (pin "2") (pinfunction "2_2") (pintype "passive"))
      (node (ref "C50") (pin "2") (pinfunction "2_2") (pintype "passive"))
      (node (ref "C51") (pin "2") (pinfunction "2_2") (pintype "passive"))
      (node (ref "C52") (pin "2") (pinfunction "2_2") (pintype "passive"))
      (node (ref "C53") (pin "2") (pinfunction "2_2") (pintype "passive"))
      (node (ref "C54") (pin "2") (pinfunction "2_2") (pintype "passive"))
      (node (ref "C61") (pin "2") (pinfunction "2_2") (pintype "passive"))
      (node (ref "C62") (pin "1") (pinfunction "1_1") (pintype "passive"))
      (node (ref "R10") (pin "2") (pinfunction "2_2") (pintype "passive"))
      (node (ref "R14") (pin "2") (pinfunction "2_2") (pintype "passive"))
      (node (ref "R17") (pin "2") (pinfunction "2_2") (pintype "passive"))
      (node (ref "R20") (pin "2") (pinfunction "2_2") (pintype "passive"))
      (node (ref "R23") (pin "2") (pinfunction "2_2") (pintype "passive"))
      (node (ref "U6") (pin "100") (pinfunction "VDD_100") (pintype "power_in"))
      (node (ref "U6") (pin "11") (pinfunction "VDD_11") (pintype "power_in"))
      (node (ref "U6") (pin "20") (pinfunction "VREF+_20") (pintype "power_in"))
      (node (ref "U6") (pin "21") (pinfunction "VDDA_21") (pintype "power_in"))
      (node (ref "U6") (pin "27") (pinfunction "VDD_27") (pintype "power_in"))
      (node (ref "U6") (pin "50") (pinfunction "VDD_50") (pintype "power_in"))
      (node (ref "U6") (pin "6") (pinfunction "VBAT_6") (pintype "power_in"))
      (node (ref "U6") (pin "75") (pinfunction "VDD_75") (pintype "power_in"))
      (node (ref "U7") (pin "2") (pinfunction "VOUT_2") (pintype "passive"))
      (node (ref "U8-1") (pin "8") (pinfunction "VCC_8") (pintype "passive"))
      (node (ref "U8-2") (pin "8") (pinfunction "VCC_8") (pintype "passive"))
      (node (ref "U8-3") (pin "8") (pinfunction "VCC_8") (pintype "passive"))
      (node (ref "U8-4") (pin "8") (pinfunction "VCC_8") (pintype "passive"))
      (node (ref "U9") (pin "1") (pinfunction "VIO_1") (pintype "passive"))
    )
    (net (code "53") (name "unconnected-(P6-Pad9)") (class "Default")
      (node (ref "P6") (pin "9") (pinfunction "9_9") (pintype "passive"))
    )
    (net (code "54") (name "unconnected-(P6-Pad10)") (class "Default")
      (node (ref "P6") (pin "10") (pinfunction "10_10") (pintype "passive"))
    )
    (net (code "55") (name "unconnected-(U6A-PA0-WKUP-Pad22)") (class "Default")
      (node (ref "U6") (pin "22") (pinfunction "PA0-WKUP_22") (pintype "bidirectional"))
    )
    (net (code "56") (name "unconnected-(U6A-PA1-Pad23)") (class "Default")
      (node (ref "U6") (pin "23") (pinfunction "PA1_23") (pintype "bidirectional"))
    )
    (net (code "57") (name "unconnected-(U6A-PA2-Pad24)") (class "Default")
      (node (ref "U6") (pin "24") (pinfunction "PA2_24") (pintype "bidirectional"))
    )
    (net (code "58") (name "unconnected-(U6A-PA3-Pad25)") (class "Default")
      (node (ref "U6") (pin "25") (pinfunction "PA3_25") (pintype "bidirectional"))
    )
    (net (code "59") (name "unconnected-(U6A-PA8-Pad67)") (class "Default")
      (node (ref "U6") (pin "67") (pinfunction "PA8_67") (pintype "bidirectional"))
    )
    (net (code "60") (name "unconnected-(U6A-PA9-Pad68)") (class "Default")
      (node (ref "U6") (pin "68") (pinfunction "PA9_68") (pintype "bidirectional"))
    )
    (net (code "61") (name "unconnected-(U6A-PA10-Pad69)") (class "Default")
      (node (ref "U6") (pin "69") (pinfunction "PA10_69") (pintype "bidirectional"))
    )
    (net (code "62") (name "unconnected-(U6A-PA11-Pad70)") (class "Default")
      (node (ref "U6") (pin "70") (pinfunction "PA11_70") (pintype "bidirectional"))
    )
    (net (code "63") (name "unconnected-(U6A-PA12-Pad71)") (class "Default")
      (node (ref "U6") (pin "71") (pinfunction "PA12_71") (pintype "bidirectional"))
    )
    (net (code "64") (name "unconnected-(U6A-PB0-Pad34)") (class "Default")
      (node (ref "U6") (pin "34") (pinfunction "PB0_34") (pintype "bidirectional"))
    )
    (net (code "65") (name "unconnected-(U6A-PB1-Pad35)") (class "Default")
      (node (ref "U6") (pin "35") (pinfunction "PB1_35") (pintype "bidirectional"))
    )
    (net (code "66") (name "unconnected-(U6A-PB2-Pad36)") (class "Default")
      (node (ref "U6") (pin "36") (pinfunction "PB2_36") (pintype "bidirectional"))
    )
    (net (code "67") (name "unconnected-(U6A-PB5-Pad91)") (class "Default")
      (node (ref "U6") (pin "91") (pinfunction "PB5_91") (pintype "bidirectional"))
    )
    (net (code "68") (name "unconnected-(U6A-PB10-Pad46)") (class "Default")
      (node (ref "U6") (pin "46") (pinfunction "PB10_46") (pintype "bidirectional"))
    )
    (net (code "69") (name "unconnected-(U6A-PB11-Pad47)") (class "Default")
      (node (ref "U6") (pin "47") (pinfunction "PB11_47") (pintype "bidirectional"))
    )
    (net (code "70") (name "unconnected-(U6A-PB12-Pad51)") (class "Default")
      (node (ref "U6") (pin "51") (pinfunction "PB12_51") (pintype "bidirectional"))
    )
    (net (code "71") (name "unconnected-(U6A-PB13-Pad52)") (class "Default")
      (node (ref "U6") (pin "52") (pinfunction "PB13_52") (pintype "bidirectional"))
    )
    (net (code "72") (name "unconnected-(U6A-PB14-Pad53)") (class "Default")
      (node (ref "U6") (pin "53") (pinfunction "PB14_53") (pintype "bidirectional"))
    )
    (net (code "73") (name "unconnected-(U6A-PB15-Pad54)") (class "Default")
      (node (ref "U6") (pin "54") (pinfunction "PB15_54") (pintype "bidirectional"))
    )
    (net (code "74") (name "unconnected-(U6A-PC0-Pad15)") (class "Default")
      (node (ref "U6") (pin "15") (pinfunction "PC0_15") (pintype "bidirectional"))
    )
    (net (code "75") (name "unconnected-(U6A-PC1-Pad16)") (class "Default")
      (node (ref "U6") (pin "16") (pinfunction "PC1_16") (pintype "bidirectional"))
    )
    (net (code "76") (name "unconnected-(U6A-PC2_C-Pad17)") (class "Default")
      (node (ref "U6") (pin "17") (pinfunction "PC2_C_17") (pintype "bidirectional"))
    )
    (net (code "77") (name "unconnected-(U6A-PC3_C-Pad18)") (class "Default")
      (node (ref "U6") (pin "18") (pinfunction "PC3_C_18") (pintype "bidirectional"))
    )
    (net (code "78") (name "unconnected-(U6A-PC4-Pad32)") (class "Default")
      (node (ref "U6") (pin "32") (pinfunction "PC4_32") (pintype "bidirectional"))
    )
    (net (code "79") (name "unconnected-(U6A-PC5-Pad33)") (class "Default")
      (node (ref "U6") (pin "33") (pinfunction "PC5_33") (pintype "bidirectional"))
    )
    (net (code "80") (name "unconnected-(U6A-PC9-Pad66)") (class "Default")
      (node (ref "U6") (pin "66") (pinfunction "PC9_66") (pintype "bidirectional"))
    )
    (net (code "81") (name "unconnected-(U6A-PC13-Pad7)") (class "Default")
      (node (ref "U6") (pin "7") (pinfunction "PC13_7") (pintype "bidirectional"))
    )
    (net (code "82") (name "unconnected-(U6A-PC14-OSC32_IN-Pad8)") (class "Default")
      (node (ref "U6") (pin "8") (pinfunction "PC14-OSC32_IN_8") (pintype "bidirectional"))
    )
    (net (code "83") (name "unconnected-(U6A-PC15-OSC32_OUT-Pad9)") (class "Default")
      (node (ref "U6") (pin "9") (pinfunction "PC15-OSC32_OUT_9") (pintype "bidirectional"))
    )
    (net (code "84") (name "unconnected-(U6A-PD0-Pad81)") (class "Default")
      (node (ref "U6") (pin "81") (pinfunction "PD0_81") (pintype "bidirectional"))
    )
    (net (code "85") (name "unconnected-(U6A-PD1-Pad82)") (class "Default")
      (node (ref "U6") (pin "82") (pinfunction "PD1_82") (pintype "bidirectional"))
    )
    (net (code "86") (name "unconnected-(U6A-PD3-Pad84)") (class "Default")
      (node (ref "U6") (pin "84") (pinfunction "PD3_84") (pintype "bidirectional"))
    )
    (net (code "87") (name "unconnected-(U6A-PD4-Pad85)") (class "Default")
      (node (ref "U6") (pin "85") (pinfunction "PD4_85") (pintype "bidirectional"))
    )
    (net (code "88") (name "unconnected-(U6A-PD7-Pad88)") (class "Default")
      (node (ref "U6") (pin "88") (pinfunction "PD7_88") (pintype "bidirectional"))
    )
    (net (code "89") (name "unconnected-(U6A-PD8-Pad55)") (class "Default")
      (node (ref "U6") (pin "55") (pinfunction "PD8_55") (pintype "bidirectional"))
    )
    (net (code "90") (name "unconnected-(U6A-PD9-Pad56)") (class "Default")
      (node (ref "U6") (pin "56") (pinfunction "PD9_56") (pintype "bidirectional"))
    )
    (net (code "91") (name "unconnected-(U6A-PD10-Pad57)") (class "Default")
      (node (ref "U6") (pin "57") (pinfunction "PD10_57") (pintype "bidirectional"))
    )
    (net (code "92") (name "unconnected-(U6A-PD11-Pad58)") (class "Default")
      (node (ref "U6") (pin "58") (pinfunction "PD11_58") (pintype "bidirectional"))
    )
    (net (code "93") (name "unconnected-(U6A-PD12-Pad59)") (class "Default")
      (node (ref "U6") (pin "59") (pinfunction "PD12_59") (pintype "bidirectional"))
    )
    (net (code "94") (name "unconnected-(U6A-PD13-Pad60)") (class "Default")
      (node (ref "U6") (pin "60") (pinfunction "PD13_60") (pintype "bidirectional"))
    )
    (net (code "95") (name "unconnected-(U6A-PD14-Pad61)") (class "Default")
      (node (ref "U6") (pin "61") (pinfunction "PD14_61") (pintype "bidirectional"))
    )
    (net (code "96") (name "unconnected-(U6B-PE4-Pad3)") (class "Default")
      (node (ref "U6") (pin "3") (pinfunction "PE4_3") (pintype "bidirectional"))
    )
    (net (code "97") (name "unconnected-(U6B-PE5-Pad4)") (class "Default")
      (node (ref "U6") (pin "4") (pinfunction "PE5_4") (pintype "bidirectional"))
    )
    (net (code "98") (name "unconnected-(U6B-PE6-Pad5)") (class "Default")
      (node (ref "U6") (pin "5") (pinfunction "PE6_5") (pintype "bidirectional"))
    )
    (net (code "99") (name "unconnected-(U6B-PE7-Pad37)") (class "Default")
      (node (ref "U6") (pin "37") (pinfunction "PE7_37") (pintype "bidirectional"))
    )
    (net (code "100") (name "unconnected-(U6B-PE8-Pad38)") (class "Default")
      (node (ref "U6") (pin "38") (pinfunction "PE8_38") (pintype "bidirectional"))
    )
    (net (code "101") (name "unconnected-(U6B-PE10-Pad40)") (class "Default")
      (node (ref "U6") (pin "40") (pinfunction "PE10_40") (pintype "bidirectional"))
    )
    (net (code "102") (name "unconnected-(U6B-PE11-Pad41)") (class "Default")
      (node (ref "U6") (pin "41") (pinfunction "PE11_41") (pintype "bidirectional"))
    )
    (net (code "103") (name "unconnected-(U6B-PE12-Pad42)") (class "Default")
      (node (ref "U6") (pin "42") (pinfunction "PE12_42") (pintype "bidirectional"))
    )
    (net (code "104") (name "unconnected-(U6B-PE13-Pad43)") (class "Default")
      (node (ref "U6") (pin "43") (pinfunction "PE13_43") (pintype "bidirectional"))
    )
    (net (code "105") (name "unconnected-(U6B-PE14-Pad44)") (class "Default")
      (node (ref "U6") (pin "44") (pinfunction "PE14_44") (pintype "bidirectional"))
    )
    (net (code "106") (name "unconnected-(U6B-PE15-Pad45)") (class "Default")
      (node (ref "U6") (pin "45") (pinfunction "PE15_45") (pintype "bidirectional"))
    )
    (net (code "107") (name "unconnected-(U8-1-EP-Pad9)") (class "Default")
      (node (ref "U8-1") (pin "9") (pinfunction "EP_9") (pintype "passive"))
    )
    (net (code "108") (name "unconnected-(U8-2-EP-Pad9)") (class "Default")
      (node (ref "U8-2") (pin "9") (pinfunction "EP_9") (pintype "passive"))
    )
    (net (code "109") (name "unconnected-(U8-3-EP-Pad9)") (class "Default")
      (node (ref "U8-3") (pin "9") (pinfunction "EP_9") (pintype "passive"))
    )
    (net (code "110") (name "unconnected-(U8-4-EP-Pad9)") (class "Default")
      (node (ref "U8-4") (pin "9") (pinfunction "EP_9") (pintype "passive"))
    )
    (net (code "111") (name "unconnected-(U9-ACT#-Pad10)") (class "Default")
      (node (ref "U9") (pin "10") (pinfunction "ACT#_10") (pintype "passive"))
    )
    (net (code "112") (name "unconnected-(U9-CTS-Pad15)") (class "Default")
      (node (ref "U9") (pin "15") (pinfunction "CTS_15") (pintype "passive"))
    )
    (net (code "113") (name "unconnected-(U9-DCD-Pad11)") (class "Default")
      (node (ref "U9") (pin "11") (pinfunction "DCD_11") (pintype "passive"))
    )
    (net (code "114") (name "unconnected-(U9-DSR-Pad14)") (class "Default")
      (node (ref "U9") (pin "14") (pinfunction "DSR_14") (pintype "passive"))
    )
    (net (code "115") (name "unconnected-(U9-DTRTNOW-Pad12)") (class "Default")
      (node (ref "U9") (pin "12") (pinfunction "DTRTNOW_12") (pintype "passive"))
    )
    (net (code "116") (name "unconnected-(U9-EP-Pad17)") (class "Default")
      (node (ref "U9") (pin "17") (pinfunction "EP_17") (pintype "passive"))
    )
    (net (code "117") (name "unconnected-(U9-RI-Pad16)") (class "Default")
      (node (ref "U9") (pin "16") (pinfunction "RI_16") (pintype "passive"))
    )
    (net (code "118") (name "unconnected-(U9-RTS-Pad13)") (class "Default")
      (node (ref "U9") (pin "13") (pinfunction "RTS_13") (pintype "passive"))
    )
    (net (code "119") (name "unconnected-(U10-SBU1-PadA8)") (class "Default")
      (node (ref "U10") (pin "A8") (pinfunction "SBU1_A8") (pintype "passive"))
    )
    (net (code "120") (name "unconnected-(U10-SBU2-PadB8)") (class "Default")
      (node (ref "U10") (pin "B8") (pinfunction "SBU2_B8") (pintype "passive"))
    )
  )
)
